# sensor-board_v1_21.net
KiCad netlist of a schematic drawn in EAGLE
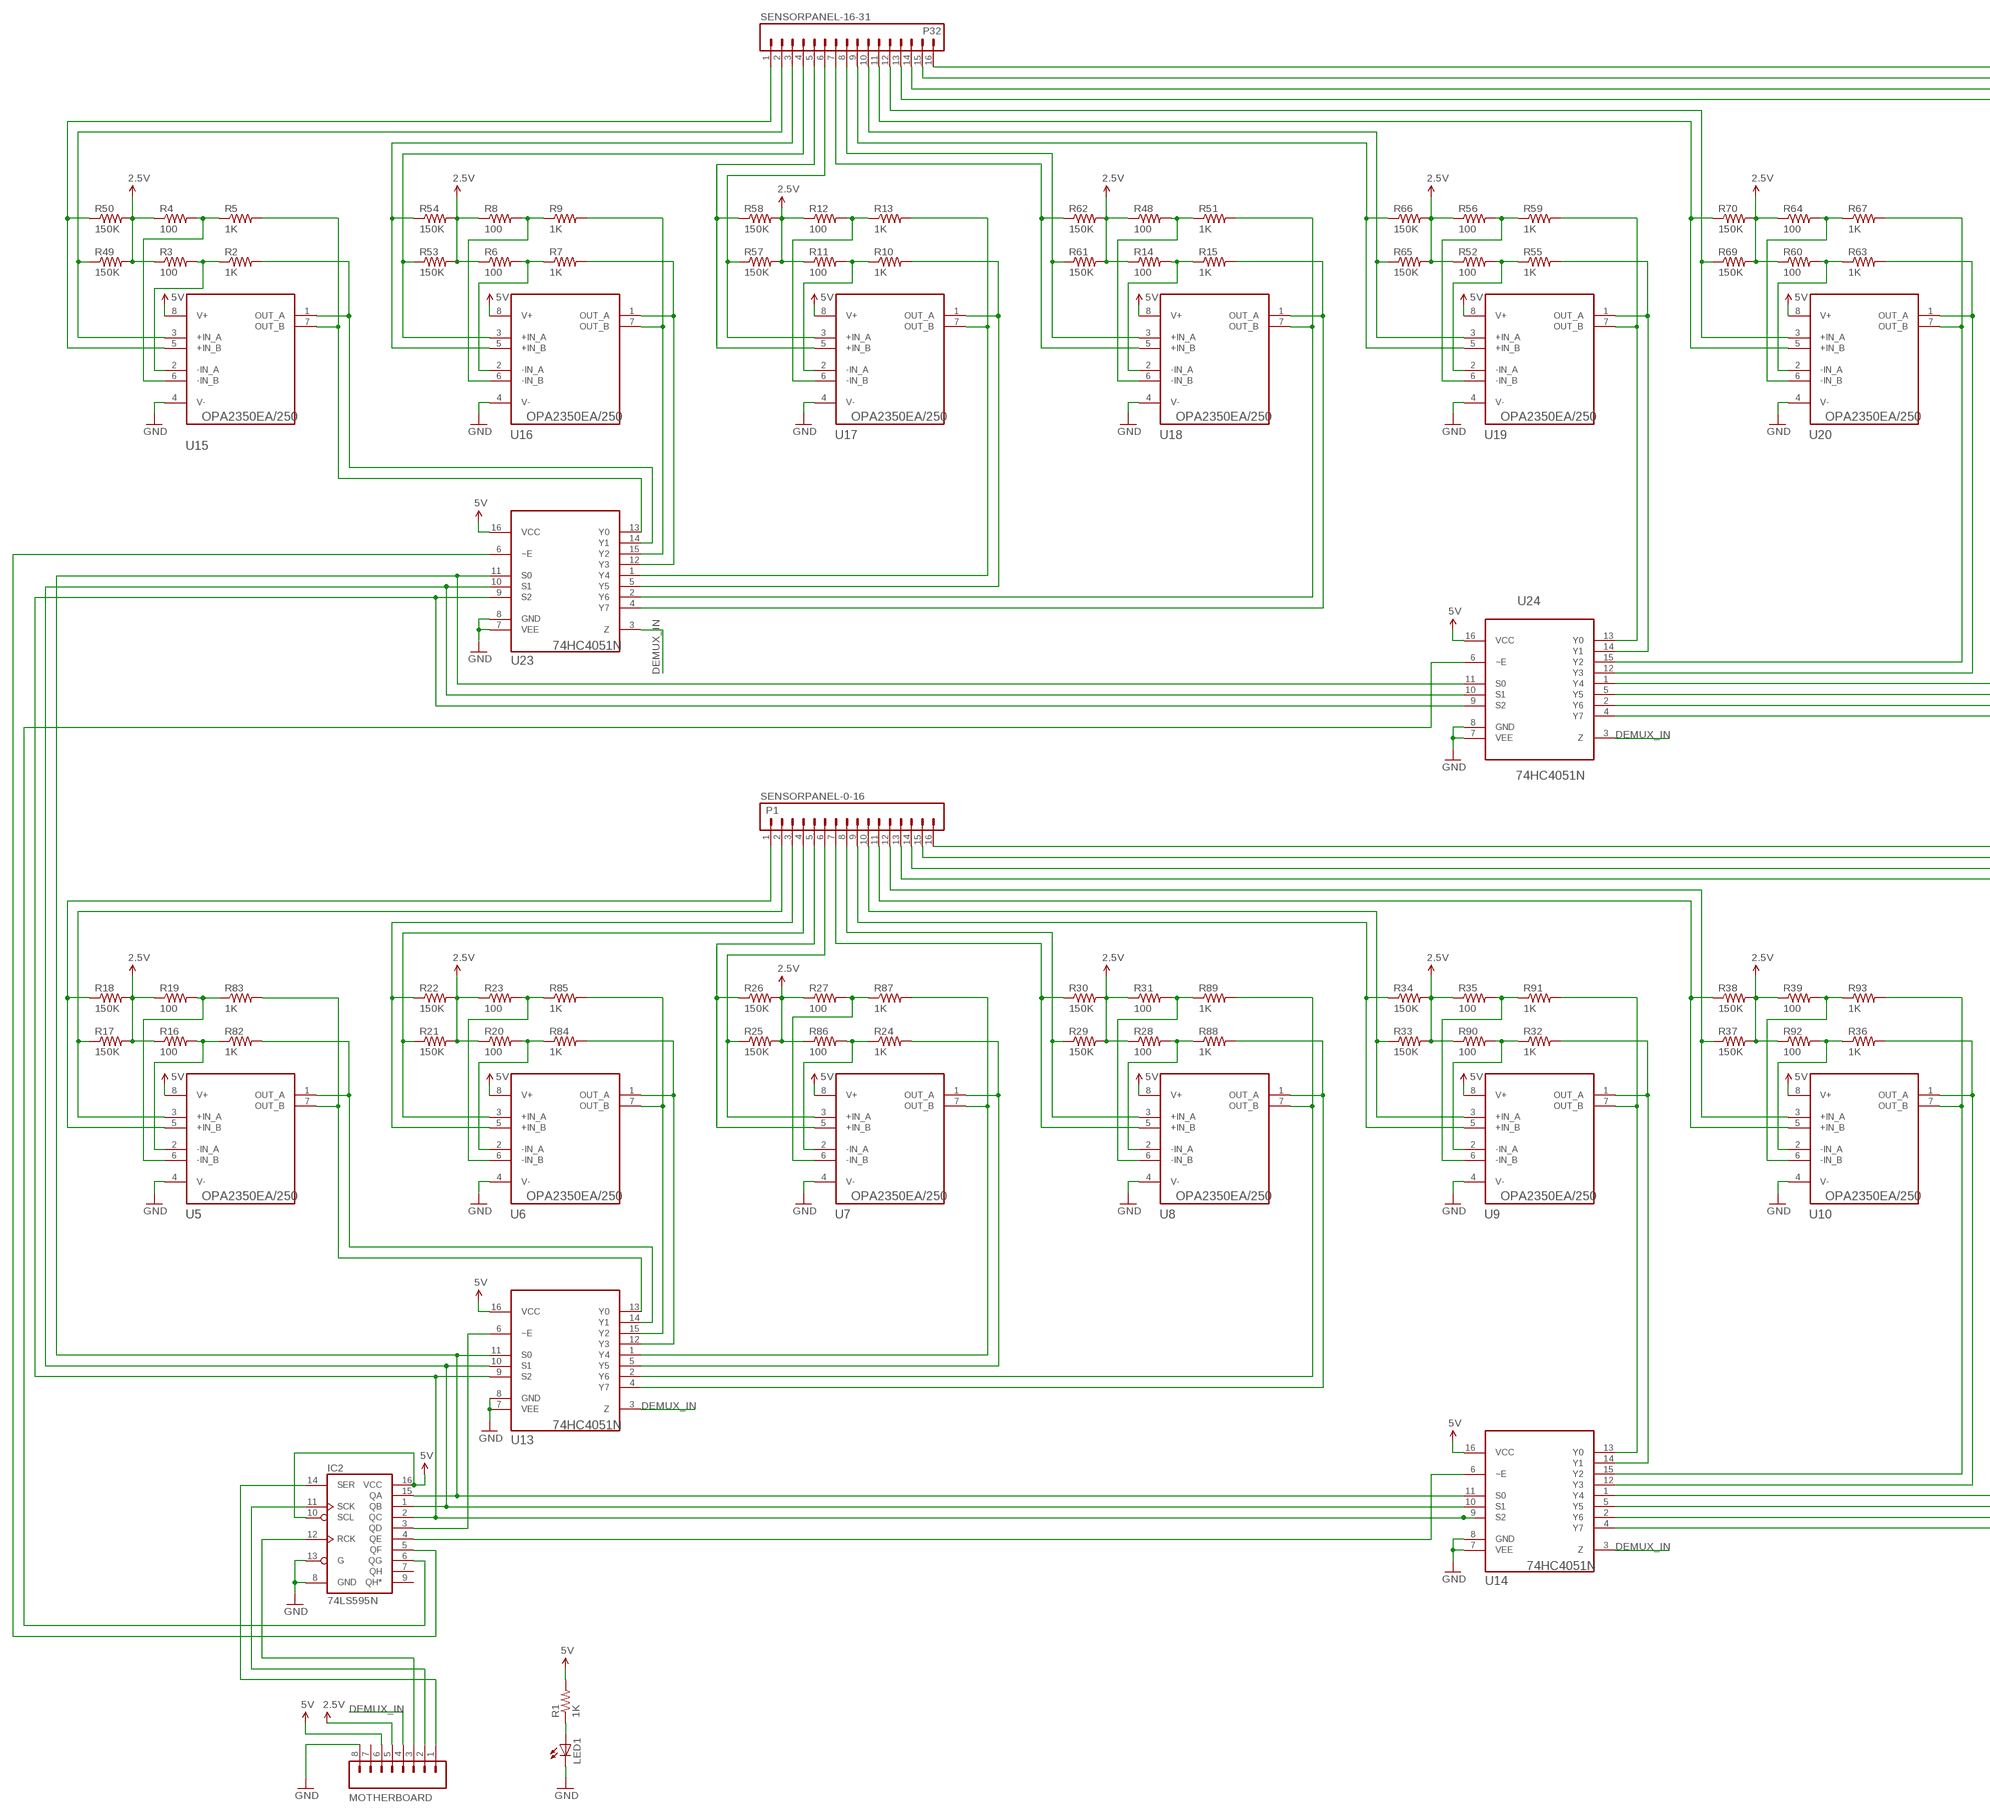
[diagram p0: schematic, sheet 1, part 1 of 2]
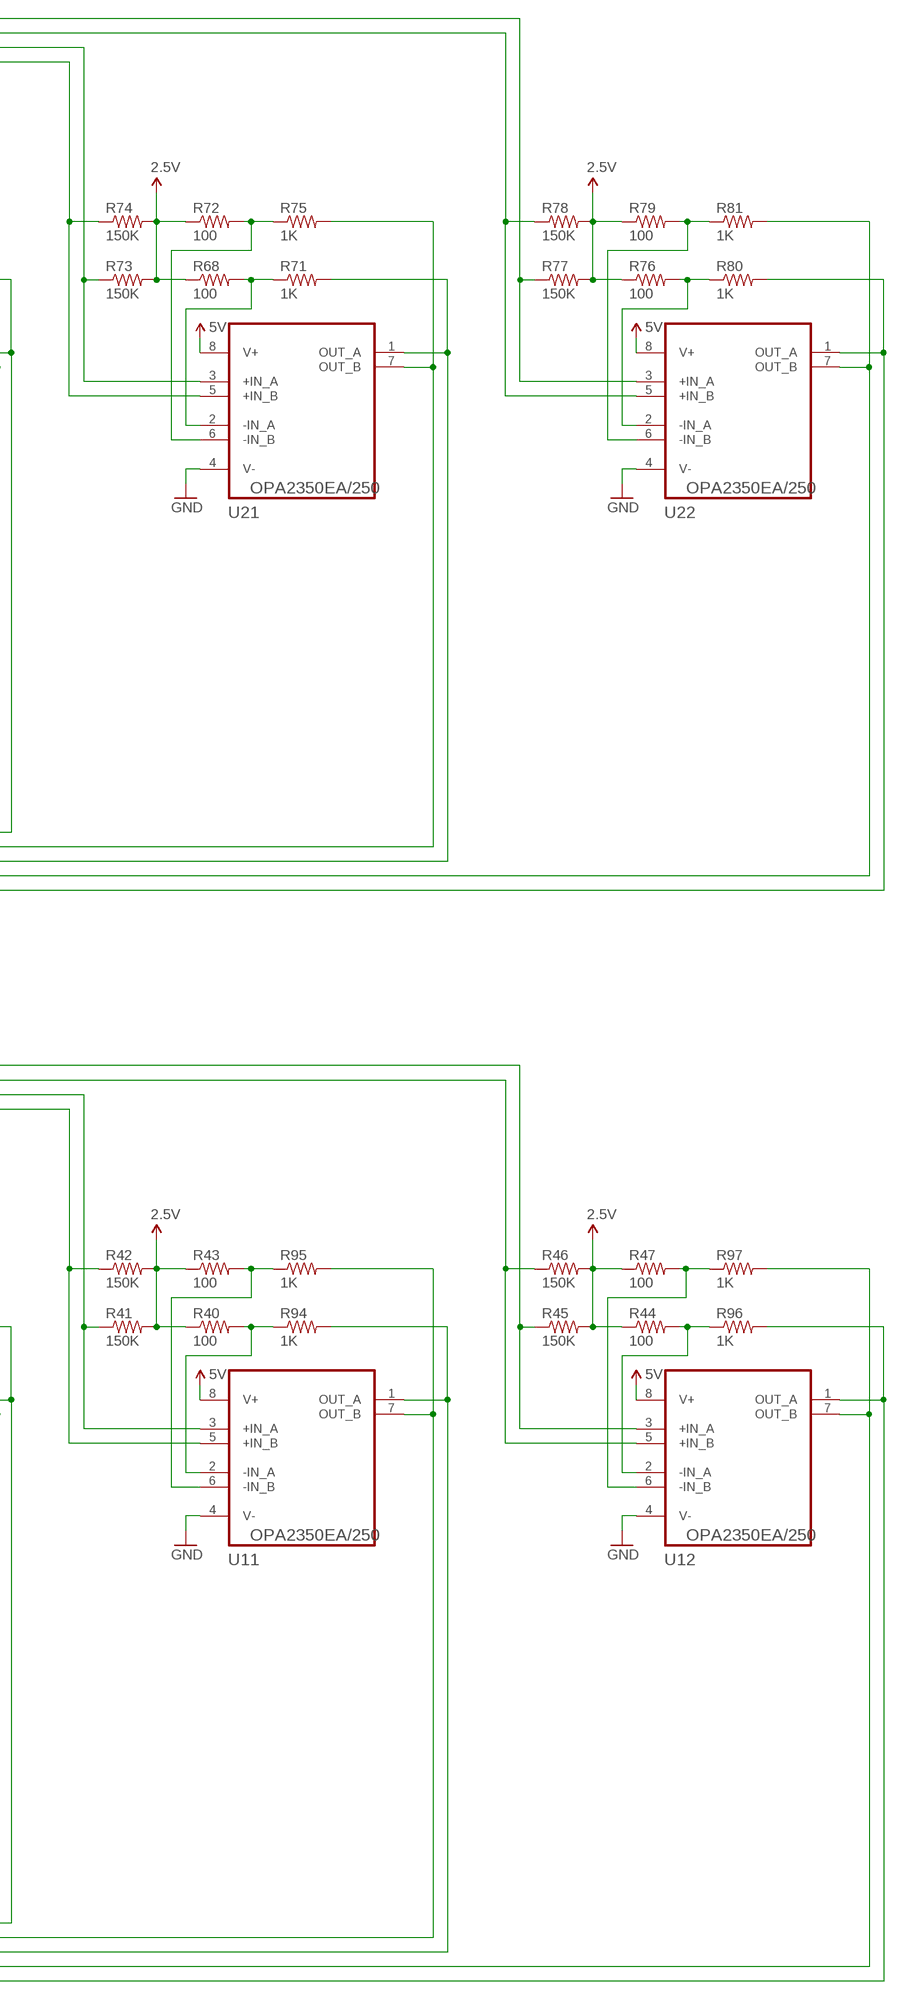
[diagram p1: schematic, sheet 1, part 2 of 2]

(export (version "E")
  (design (tool "Eeschema 10.0.6"))
  (components
    (comp (ref "IC2")
      (value "74LS595N")
      (footprint "eagle-import:DIL16")
      (libsource (lib "eagle-import") (part "74595NLS"))
    )
    (comp (ref "LED1")
      (value "LED0603")
      (footprint "eagle-import:LED-0603")
      (libsource (lib "eagle-import") (part "LED0603"))
    )
    (comp (ref "MOTHERBOARD")
      (value "M08LONGPADS")
      (footprint "eagle-import:1X08_LONGPADS")
      (libsource (lib "eagle-import") (part "M08LONGPADS"))
    )
    (comp (ref "R1")
      (value "1K")
      (footprint "eagle-import:0805")
      (libsource (lib "eagle-import") (part "RESISTOR0805-RES"))
    )
    (comp (ref "R2")
      (value "1K")
      (footprint "eagle-import:0805")
      (libsource (lib "eagle-import") (part "RESISTOR0805-RES"))
    )
    (comp (ref "R3")
      (value "100")
      (footprint "eagle-import:0805")
      (libsource (lib "eagle-import") (part "RESISTOR0805-RES"))
    )
    (comp (ref "R4")
      (value "100")
      (footprint "eagle-import:0805")
      (libsource (lib "eagle-import") (part "RESISTOR0805-RES"))
    )
    (comp (ref "R5")
      (value "1K")
      (footprint "eagle-import:0805")
      (libsource (lib "eagle-import") (part "RESISTOR0805-RES"))
    )
    (comp (ref "R6")
      (value "100")
      (footprint "eagle-import:0805")
      (libsource (lib "eagle-import") (part "RESISTOR0805-RES"))
    )
    (comp (ref "R7")
      (value "1K")
      (footprint "eagle-import:0805")
      (libsource (lib "eagle-import") (part "RESISTOR0805-RES"))
    )
    (comp (ref "R8")
      (value "100")
      (footprint "eagle-import:0805")
      (libsource (lib "eagle-import") (part "RESISTOR0805-RES"))
    )
    (comp (ref "R9")
      (value "1K")
      (footprint "eagle-import:0805")
      (libsource (lib "eagle-import") (part "RESISTOR0805-RES"))
    )
    (comp (ref "R10")
      (value "1K")
      (footprint "eagle-import:0805")
      (libsource (lib "eagle-import") (part "RESISTOR0805-RES"))
    )
    (comp (ref "R11")
      (value "100")
      (footprint "eagle-import:0805")
      (libsource (lib "eagle-import") (part "RESISTOR0805-RES"))
    )
    (comp (ref "R12")
      (value "100")
      (footprint "eagle-import:0805")
      (libsource (lib "eagle-import") (part "RESISTOR0805-RES"))
    )
    (comp (ref "R13")
      (value "1K")
      (footprint "eagle-import:0805")
      (libsource (lib "eagle-import") (part "RESISTOR0805-RES"))
    )
    (comp (ref "R14")
      (value "100")
      (footprint "eagle-import:0805")
      (libsource (lib "eagle-import") (part "RESISTOR0805-RES"))
    )
    (comp (ref "R15")
      (value "1K")
      (footprint "eagle-import:0805")
      (libsource (lib "eagle-import") (part "RESISTOR0805-RES"))
    )
    (comp (ref "R16")
      (value "100")
      (footprint "eagle-import:0805")
      (libsource (lib "eagle-import") (part "RESISTOR0805-RES"))
    )
    (comp (ref "R17")
      (value "150K")
      (footprint "eagle-import:0805")
      (libsource (lib "eagle-import") (part "RESISTOR0805-RES"))
    )
    (comp (ref "R18")
      (value "150K")
      (footprint "eagle-import:0805")
      (libsource (lib "eagle-import") (part "RESISTOR0805-RES"))
    )
    (comp (ref "R19")
      (value "100")
      (footprint "eagle-import:0805")
      (libsource (lib "eagle-import") (part "RESISTOR0805-RES"))
    )
    (comp (ref "R20")
      (value "100")
      (footprint "eagle-import:0805")
      (libsource (lib "eagle-import") (part "RESISTOR0805-RES"))
    )
    (comp (ref "R21")
      (value "150K")
      (footprint "eagle-import:0805")
      (libsource (lib "eagle-import") (part "RESISTOR0805-RES"))
    )
    (comp (ref "R22")
      (value "150K")
      (footprint "eagle-import:0805")
      (libsource (lib "eagle-import") (part "RESISTOR0805-RES"))
    )
    (comp (ref "R23")
      (value "100")
      (footprint "eagle-import:0805")
      (libsource (lib "eagle-import") (part "RESISTOR0805-RES"))
    )
    (comp (ref "R24")
      (value "1K")
      (footprint "eagle-import:0805")
      (libsource (lib "eagle-import") (part "RESISTOR0805-RES"))
    )
    (comp (ref "R25")
      (value "150K")
      (footprint "eagle-import:0805")
      (libsource (lib "eagle-import") (part "RESISTOR0805-RES"))
    )
    (comp (ref "R26")
      (value "150K")
      (footprint "eagle-import:0805")
      (libsource (lib "eagle-import") (part "RESISTOR0805-RES"))
    )
    (comp (ref "R27")
      (value "100")
      (footprint "eagle-import:0805")
      (libsource (lib "eagle-import") (part "RESISTOR0805-RES"))
    )
    (comp (ref "R28")
      (value "100")
      (footprint "eagle-import:0805")
      (libsource (lib "eagle-import") (part "RESISTOR0805-RES"))
    )
    (comp (ref "R29")
      (value "150K")
      (footprint "eagle-import:0805")
      (libsource (lib "eagle-import") (part "RESISTOR0805-RES"))
    )
    (comp (ref "R30")
      (value "150K")
      (footprint "eagle-import:0805")
      (libsource (lib "eagle-import") (part "RESISTOR0805-RES"))
    )
    (comp (ref "R31")
      (value "100")
      (footprint "eagle-import:0805")
      (libsource (lib "eagle-import") (part "RESISTOR0805-RES"))
    )
    (comp (ref "R32")
      (value "1K")
      (footprint "eagle-import:0805")
      (libsource (lib "eagle-import") (part "RESISTOR0805-RES"))
    )
    (comp (ref "R33")
      (value "150K")
      (footprint "eagle-import:0805")
      (libsource (lib "eagle-import") (part "RESISTOR0805-RES"))
    )
    (comp (ref "R34")
      (value "150K")
      (footprint "eagle-import:0805")
      (libsource (lib "eagle-import") (part "RESISTOR0805-RES"))
    )
    (comp (ref "R35")
      (value "100")
      (footprint "eagle-import:0805")
      (libsource (lib "eagle-import") (part "RESISTOR0805-RES"))
    )
    (comp (ref "R36")
      (value "1K")
      (footprint "eagle-import:0805")
      (libsource (lib "eagle-import") (part "RESISTOR0805-RES"))
    )
    (comp (ref "R37")
      (value "150K")
      (footprint "eagle-import:0805")
      (libsource (lib "eagle-import") (part "RESISTOR0805-RES"))
    )
    (comp (ref "R38")
      (value "150K")
      (footprint "eagle-import:0805")
      (libsource (lib "eagle-import") (part "RESISTOR0805-RES"))
    )
    (comp (ref "R39")
      (value "100")
      (footprint "eagle-import:0805")
      (libsource (lib "eagle-import") (part "RESISTOR0805-RES"))
    )
    (comp (ref "R40")
      (value "100")
      (footprint "eagle-import:0805")
      (libsource (lib "eagle-import") (part "RESISTOR0805-RES"))
    )
    (comp (ref "R41")
      (value "150K")
      (footprint "eagle-import:0805")
      (libsource (lib "eagle-import") (part "RESISTOR0805-RES"))
    )
    (comp (ref "R42")
      (value "150K")
      (footprint "eagle-import:0805")
      (libsource (lib "eagle-import") (part "RESISTOR0805-RES"))
    )
    (comp (ref "R43")
      (value "100")
      (footprint "eagle-import:0805")
      (libsource (lib "eagle-import") (part "RESISTOR0805-RES"))
    )
    (comp (ref "R44")
      (value "100")
      (footprint "eagle-import:0805")
      (libsource (lib "eagle-import") (part "RESISTOR0805-RES"))
    )
    (comp (ref "R45")
      (value "150K")
      (footprint "eagle-import:0805")
      (libsource (lib "eagle-import") (part "RESISTOR0805-RES"))
    )
    (comp (ref "R46")
      (value "150K")
      (footprint "eagle-import:0805")
      (libsource (lib "eagle-import") (part "RESISTOR0805-RES"))
    )
    (comp (ref "R47")
      (value "100")
      (footprint "eagle-import:0805")
      (libsource (lib "eagle-import") (part "RESISTOR0805-RES"))
    )
    (comp (ref "R48")
      (value "100")
      (footprint "eagle-import:0805")
      (libsource (lib "eagle-import") (part "RESISTOR0805-RES"))
    )
    (comp (ref "R49")
      (value "150K")
      (footprint "eagle-import:0805")
      (libsource (lib "eagle-import") (part "RESISTOR0805-RES"))
    )
    (comp (ref "R50")
      (value "150K")
      (footprint "eagle-import:0805")
      (libsource (lib "eagle-import") (part "RESISTOR0805-RES"))
    )
    (comp (ref "R51")
      (value "1K")
      (footprint "eagle-import:0805")
      (libsource (lib "eagle-import") (part "RESISTOR0805-RES"))
    )
    (comp (ref "R52")
      (value "100")
      (footprint "eagle-import:0805")
      (libsource (lib "eagle-import") (part "RESISTOR0805-RES"))
    )
    (comp (ref "R53")
      (value "150K")
      (footprint "eagle-import:0805")
      (libsource (lib "eagle-import") (part "RESISTOR0805-RES"))
    )
    (comp (ref "R54")
      (value "150K")
      (footprint "eagle-import:0805")
      (libsource (lib "eagle-import") (part "RESISTOR0805-RES"))
    )
    (comp (ref "R55")
      (value "1K")
      (footprint "eagle-import:0805")
      (libsource (lib "eagle-import") (part "RESISTOR0805-RES"))
    )
    (comp (ref "R56")
      (value "100")
      (footprint "eagle-import:0805")
      (libsource (lib "eagle-import") (part "RESISTOR0805-RES"))
    )
    (comp (ref "R57")
      (value "150K")
      (footprint "eagle-import:0805")
      (libsource (lib "eagle-import") (part "RESISTOR0805-RES"))
    )
    (comp (ref "R58")
      (value "150K")
      (footprint "eagle-import:0805")
      (libsource (lib "eagle-import") (part "RESISTOR0805-RES"))
    )
    (comp (ref "R59")
      (value "1K")
      (footprint "eagle-import:0805")
      (libsource (lib "eagle-import") (part "RESISTOR0805-RES"))
    )
    (comp (ref "R60")
      (value "100")
      (footprint "eagle-import:0805")
      (libsource (lib "eagle-import") (part "RESISTOR0805-RES"))
    )
    (comp (ref "R61")
      (value "150K")
      (footprint "eagle-import:0805")
      (libsource (lib "eagle-import") (part "RESISTOR0805-RES"))
    )
    (comp (ref "R62")
      (value "150K")
      (footprint "eagle-import:0805")
      (libsource (lib "eagle-import") (part "RESISTOR0805-RES"))
    )
    (comp (ref "R63")
      (value "1K")
      (footprint "eagle-import:0805")
      (libsource (lib "eagle-import") (part "RESISTOR0805-RES"))
    )
    (comp (ref "R64")
      (value "100")
      (footprint "eagle-import:0805")
      (libsource (lib "eagle-import") (part "RESISTOR0805-RES"))
    )
    (comp (ref "R65")
      (value "150K")
      (footprint "eagle-import:0805")
      (libsource (lib "eagle-import") (part "RESISTOR0805-RES"))
    )
    (comp (ref "R66")
      (value "150K")
      (footprint "eagle-import:0805")
      (libsource (lib "eagle-import") (part "RESISTOR0805-RES"))
    )
    (comp (ref "R67")
      (value "1K")
      (footprint "eagle-import:0805")
      (libsource (lib "eagle-import") (part "RESISTOR0805-RES"))
    )
    (comp (ref "R68")
      (value "100")
      (footprint "eagle-import:0805")
      (libsource (lib "eagle-import") (part "RESISTOR0805-RES"))
    )
    (comp (ref "R69")
      (value "150K")
      (footprint "eagle-import:0805")
      (libsource (lib "eagle-import") (part "RESISTOR0805-RES"))
    )
    (comp (ref "R70")
      (value "150K")
      (footprint "eagle-import:0805")
      (libsource (lib "eagle-import") (part "RESISTOR0805-RES"))
    )
    (comp (ref "R71")
      (value "1K")
      (footprint "eagle-import:0805")
      (libsource (lib "eagle-import") (part "RESISTOR0805-RES"))
    )
    (comp (ref "R72")
      (value "100")
      (footprint "eagle-import:0805")
      (libsource (lib "eagle-import") (part "RESISTOR0805-RES"))
    )
    (comp (ref "R73")
      (value "150K")
      (footprint "eagle-import:0805")
      (libsource (lib "eagle-import") (part "RESISTOR0805-RES"))
    )
    (comp (ref "R74")
      (value "150K")
      (footprint "eagle-import:0805")
      (libsource (lib "eagle-import") (part "RESISTOR0805-RES"))
    )
    (comp (ref "R75")
      (value "1K")
      (footprint "eagle-import:0805")
      (libsource (lib "eagle-import") (part "RESISTOR0805-RES"))
    )
    (comp (ref "R76")
      (value "100")
      (footprint "eagle-import:0805")
      (libsource (lib "eagle-import") (part "RESISTOR0805-RES"))
    )
    (comp (ref "R77")
      (value "150K")
      (footprint "eagle-import:0805")
      (libsource (lib "eagle-import") (part "RESISTOR0805-RES"))
    )
    (comp (ref "R78")
      (value "150K")
      (footprint "eagle-import:0805")
      (libsource (lib "eagle-import") (part "RESISTOR0805-RES"))
    )
    (comp (ref "R79")
      (value "100")
      (footprint "eagle-import:0805")
      (libsource (lib "eagle-import") (part "RESISTOR0805-RES"))
    )
    (comp (ref "R80")
      (value "1K")
      (footprint "eagle-import:0805")
      (libsource (lib "eagle-import") (part "RESISTOR0805-RES"))
    )
    (comp (ref "R81")
      (value "1K")
      (footprint "eagle-import:0805")
      (libsource (lib "eagle-import") (part "RESISTOR0805-RES"))
    )
    (comp (ref "R82")
      (value "1K")
      (footprint "eagle-import:0805")
      (libsource (lib "eagle-import") (part "RESISTOR0805-RES"))
    )
    (comp (ref "R83")
      (value "1K")
      (footprint "eagle-import:0805")
      (libsource (lib "eagle-import") (part "RESISTOR0805-RES"))
    )
    (comp (ref "R84")
      (value "1K")
      (footprint "eagle-import:0805")
      (libsource (lib "eagle-import") (part "RESISTOR0805-RES"))
    )
    (comp (ref "R85")
      (value "1K")
      (footprint "eagle-import:0805")
      (libsource (lib "eagle-import") (part "RESISTOR0805-RES"))
    )
    (comp (ref "R86")
      (value "100")
      (footprint "eagle-import:0805")
      (libsource (lib "eagle-import") (part "RESISTOR0805-RES"))
    )
    (comp (ref "R87")
      (value "1K")
      (footprint "eagle-import:0805")
      (libsource (lib "eagle-import") (part "RESISTOR0805-RES"))
    )
    (comp (ref "R88")
      (value "1K")
      (footprint "eagle-import:0805")
      (libsource (lib "eagle-import") (part "RESISTOR0805-RES"))
    )
    (comp (ref "R89")
      (value "1K")
      (footprint "eagle-import:0805")
      (libsource (lib "eagle-import") (part "RESISTOR0805-RES"))
    )
    (comp (ref "R90")
      (value "100")
      (footprint "eagle-import:0805")
      (libsource (lib "eagle-import") (part "RESISTOR0805-RES"))
    )
    (comp (ref "R91")
      (value "1K")
      (footprint "eagle-import:0805")
      (libsource (lib "eagle-import") (part "RESISTOR0805-RES"))
    )
    (comp (ref "R92")
      (value "100")
      (footprint "eagle-import:0805")
      (libsource (lib "eagle-import") (part "RESISTOR0805-RES"))
    )
    (comp (ref "R93")
      (value "1K")
      (footprint "eagle-import:0805")
      (libsource (lib "eagle-import") (part "RESISTOR0805-RES"))
    )
    (comp (ref "R94")
      (value "1K")
      (footprint "eagle-import:0805")
      (libsource (lib "eagle-import") (part "RESISTOR0805-RES"))
    )
    (comp (ref "R95")
      (value "1K")
      (footprint "eagle-import:0805")
      (libsource (lib "eagle-import") (part "RESISTOR0805-RES"))
    )
    (comp (ref "R96")
      (value "1K")
      (footprint "eagle-import:0805")
      (libsource (lib "eagle-import") (part "RESISTOR0805-RES"))
    )
    (comp (ref "R97")
      (value "1K")
      (footprint "eagle-import:0805")
      (libsource (lib "eagle-import") (part "RESISTOR0805-RES"))
    )
    (comp (ref "SENSORPANEL-0-16")
      (value "P1")
      (footprint "eagle-import:1X16_LOCK")
      (libsource (lib "eagle-import") (part "M16LOCK"))
    )
    (comp (ref "SENSORPANEL-16-31")
      (value "P32")
      (footprint "eagle-import:1X16_LOCK")
      (libsource (lib "eagle-import") (part "M16LOCK"))
    )
    (comp (ref "U5")
      (value "OPA2350EA/250")
      (footprint "eagle-import:SOP65P490X110-8N")
      (libsource (lib "eagle-import") (part "OPA2350EA/250"))
    )
    (comp (ref "U6")
      (value "OPA2350EA/250")
      (footprint "eagle-import:SOP65P490X110-8N")
      (libsource (lib "eagle-import") (part "OPA2350EA/250"))
    )
    (comp (ref "U7")
      (value "OPA2350EA/250")
      (footprint "eagle-import:SOP65P490X110-8N")
      (libsource (lib "eagle-import") (part "OPA2350EA/250"))
    )
    (comp (ref "U8")
      (value "OPA2350EA/250")
      (footprint "eagle-import:SOP65P490X110-8N")
      (libsource (lib "eagle-import") (part "OPA2350EA/250"))
    )
    (comp (ref "U9")
      (value "OPA2350EA/250")
      (footprint "eagle-import:SOP65P490X110-8N")
      (libsource (lib "eagle-import") (part "OPA2350EA/250"))
    )
    (comp (ref "U10")
      (value "OPA2350EA/250")
      (footprint "eagle-import:SOP65P490X110-8N")
      (libsource (lib "eagle-import") (part "OPA2350EA/250"))
    )
    (comp (ref "U11")
      (value "OPA2350EA/250")
      (footprint "eagle-import:SOP65P490X110-8N")
      (libsource (lib "eagle-import") (part "OPA2350EA/250"))
    )
    (comp (ref "U12")
      (value "OPA2350EA/250")
      (footprint "eagle-import:SOP65P490X110-8N")
      (libsource (lib "eagle-import") (part "OPA2350EA/250"))
    )
    (comp (ref "U13")
      (value "74HC4051N")
      (footprint "eagle-import:DIP254P762X420-16")
      (libsource (lib "eagle-import") (part "74HC4051N"))
    )
    (comp (ref "U14")
      (value "74HC4051N")
      (footprint "eagle-import:DIP254P762X420-16")
      (libsource (lib "eagle-import") (part "74HC4051N"))
    )
    (comp (ref "U15")
      (value "OPA2350EA/250")
      (footprint "eagle-import:SOP65P490X110-8N")
      (libsource (lib "eagle-import") (part "OPA2350EA/250"))
    )
    (comp (ref "U16")
      (value "OPA2350EA/250")
      (footprint "eagle-import:SOP65P490X110-8N")
      (libsource (lib "eagle-import") (part "OPA2350EA/250"))
    )
    (comp (ref "U17")
      (value "OPA2350EA/250")
      (footprint "eagle-import:SOP65P490X110-8N")
      (libsource (lib "eagle-import") (part "OPA2350EA/250"))
    )
    (comp (ref "U18")
      (value "OPA2350EA/250")
      (footprint "eagle-import:SOP65P490X110-8N")
      (libsource (lib "eagle-import") (part "OPA2350EA/250"))
    )
    (comp (ref "U19")
      (value "OPA2350EA/250")
      (footprint "eagle-import:SOP65P490X110-8N")
      (libsource (lib "eagle-import") (part "OPA2350EA/250"))
    )
    (comp (ref "U20")
      (value "OPA2350EA/250")
      (footprint "eagle-import:SOP65P490X110-8N")
      (libsource (lib "eagle-import") (part "OPA2350EA/250"))
    )
    (comp (ref "U21")
      (value "OPA2350EA/250")
      (footprint "eagle-import:SOP65P490X110-8N")
      (libsource (lib "eagle-import") (part "OPA2350EA/250"))
    )
    (comp (ref "U22")
      (value "OPA2350EA/250")
      (footprint "eagle-import:SOP65P490X110-8N")
      (libsource (lib "eagle-import") (part "OPA2350EA/250"))
    )
    (comp (ref "U23")
      (value "74HC4051N")
      (footprint "eagle-import:DIP254P762X420-16")
      (libsource (lib "eagle-import") (part "74HC4051N"))
    )
    (comp (ref "U24")
      (value "74HC4051N")
      (footprint "eagle-import:DIP254P762X420-16")
      (libsource (lib "eagle-import") (part "74HC4051N"))
    )
  )
  (nets
    (net (code "1") (name "/DEMUX_IN") (class "Default")
      (node (ref "MOTHERBOARD") (pin "4") (pinfunction "4_4") (pintype "passive"))
      (node (ref "U13") (pin "3") (pinfunction "Z_3") (pintype "bidirectional"))
      (node (ref "U14") (pin "3") (pinfunction "Z_3") (pintype "bidirectional"))
      (node (ref "U23") (pin "3") (pinfunction "Z_3") (pintype "bidirectional"))
      (node (ref "U24") (pin "3") (pinfunction "Z_3") (pintype "bidirectional"))
    )
    (net (code "2") (name "2.5V") (class "Default")
      (node (ref "MOTHERBOARD") (pin "5") (pinfunction "5_5") (pintype "passive"))
      (node (ref "R11") (pin "1") (pinfunction "1_1") (pintype "passive"))
      (node (ref "R12") (pin "1") (pinfunction "1_1") (pintype "passive"))
      (node (ref "R14") (pin "1") (pinfunction "1_1") (pintype "passive"))
      (node (ref "R16") (pin "1") (pinfunction "1_1") (pintype "passive"))
      (node (ref "R17") (pin "2") (pinfunction "2_2") (pintype "passive"))
      (node (ref "R18") (pin "2") (pinfunction "2_2") (pintype "passive"))
      (node (ref "R19") (pin "1") (pinfunction "1_1") (pintype "passive"))
      (node (ref "R20") (pin "1") (pinfunction "1_1") (pintype "passive"))
      (node (ref "R21") (pin "2") (pinfunction "2_2") (pintype "passive"))
      (node (ref "R22") (pin "2") (pinfunction "2_2") (pintype "passive"))
      (node (ref "R23") (pin "1") (pinfunction "1_1") (pintype "passive"))
      (node (ref "R25") (pin "2") (pinfunction "2_2") (pintype "passive"))
      (node (ref "R26") (pin "2") (pinfunction "2_2") (pintype "passive"))
      (node (ref "R27") (pin "1") (pinfunction "1_1") (pintype "passive"))
      (node (ref "R28") (pin "1") (pinfunction "1_1") (pintype "passive"))
      (node (ref "R29") (pin "2") (pinfunction "2_2") (pintype "passive"))
      (node (ref "R3") (pin "1") (pinfunction "1_1") (pintype "passive"))
      (node (ref "R30") (pin "2") (pinfunction "2_2") (pintype "passive"))
      (node (ref "R31") (pin "1") (pinfunction "1_1") (pintype "passive"))
      (node (ref "R33") (pin "2") (pinfunction "2_2") (pintype "passive"))
      (node (ref "R34") (pin "2") (pinfunction "2_2") (pintype "passive"))
      (node (ref "R35") (pin "1") (pinfunction "1_1") (pintype "passive"))
      (node (ref "R37") (pin "2") (pinfunction "2_2") (pintype "passive"))
      (node (ref "R38") (pin "2") (pinfunction "2_2") (pintype "passive"))
      (node (ref "R39") (pin "1") (pinfunction "1_1") (pintype "passive"))
      (node (ref "R4") (pin "1") (pinfunction "1_1") (pintype "passive"))
      (node (ref "R40") (pin "1") (pinfunction "1_1") (pintype "passive"))
      (node (ref "R41") (pin "2") (pinfunction "2_2") (pintype "passive"))
      (node (ref "R42") (pin "2") (pinfunction "2_2") (pintype "passive"))
      (node (ref "R43") (pin "1") (pinfunction "1_1") (pintype "passive"))
      (node (ref "R44") (pin "1") (pinfunction "1_1") (pintype "passive"))
      (node (ref "R45") (pin "2") (pinfunction "2_2") (pintype "passive"))
      (node (ref "R46") (pin "2") (pinfunction "2_2") (pintype "passive"))
      (node (ref "R47") (pin "1") (pinfunction "1_1") (pintype "passive"))
      (node (ref "R48") (pin "1") (pinfunction "1_1") (pintype "passive"))
      (node (ref "R49") (pin "2") (pinfunction "2_2") (pintype "passive"))
      (node (ref "R50") (pin "2") (pinfunction "2_2") (pintype "passive"))
      (node (ref "R52") (pin "1") (pinfunction "1_1") (pintype "passive"))
      (node (ref "R53") (pin "2") (pinfunction "2_2") (pintype "passive"))
      (node (ref "R54") (pin "2") (pinfunction "2_2") (pintype "passive"))
      (node (ref "R56") (pin "1") (pinfunction "1_1") (pintype "passive"))
      (node (ref "R57") (pin "2") (pinfunction "2_2") (pintype "passive"))
      (node (ref "R58") (pin "2") (pinfunction "2_2") (pintype "passive"))
      (node (ref "R6") (pin "1") (pinfunction "1_1") (pintype "passive"))
      (node (ref "R60") (pin "1") (pinfunction "1_1") (pintype "passive"))
      (node (ref "R61") (pin "2") (pinfunction "2_2") (pintype "passive"))
      (node (ref "R62") (pin "2") (pinfunction "2_2") (pintype "passive"))
      (node (ref "R64") (pin "1") (pinfunction "1_1") (pintype "passive"))
      (node (ref "R65") (pin "2") (pinfunction "2_2") (pintype "passive"))
      (node (ref "R66") (pin "2") (pinfunction "2_2") (pintype "passive"))
      (node (ref "R68") (pin "1") (pinfunction "1_1") (pintype "passive"))
      (node (ref "R69") (pin "2") (pinfunction "2_2") (pintype "passive"))
      (node (ref "R70") (pin "2") (pinfunction "2_2") (pintype "passive"))
      (node (ref "R72") (pin "1") (pinfunction "1_1") (pintype "passive"))
      (node (ref "R73") (pin "2") (pinfunction "2_2") (pintype "passive"))
      (node (ref "R74") (pin "2") (pinfunction "2_2") (pintype "passive"))
      (node (ref "R76") (pin "1") (pinfunction "1_1") (pintype "passive"))
      (node (ref "R77") (pin "2") (pinfunction "2_2") (pintype "passive"))
      (node (ref "R78") (pin "2") (pinfunction "2_2") (pintype "passive"))
      (node (ref "R79") (pin "1") (pinfunction "1_1") (pintype "passive"))
      (node (ref "R8") (pin "1") (pinfunction "1_1") (pintype "passive"))
      (node (ref "R86") (pin "1") (pinfunction "1_1") (pintype "passive"))
      (node (ref "R90") (pin "1") (pinfunction "1_1") (pintype "passive"))
      (node (ref "R92") (pin "1") (pinfunction "1_1") (pintype "passive"))
    )
    (net (code "3") (name "5V") (class "Default")
      (node (ref "IC2") (pin "10") (pinfunction "SCL_10") (pintype "input"))
      (node (ref "IC2") (pin "16") (pinfunction "VCC_16") (pintype "power_in"))
      (node (ref "MOTHERBOARD") (pin "6") (pinfunction "6_6") (pintype "passive"))
      (node (ref "R1") (pin "2") (pinfunction "2_2") (pintype "passive"))
      (node (ref "U10") (pin "8") (pinfunction "V+_8") (pintype "power_in"))
      (node (ref "U11") (pin "8") (pinfunction "V+_8") (pintype "power_in"))
      (node (ref "U12") (pin "8") (pinfunction "V+_8") (pintype "power_in"))
      (node (ref "U13") (pin "16") (pinfunction "VCC_16") (pintype "power_in"))
      (node (ref "U14") (pin "16") (pinfunction "VCC_16") (pintype "power_in"))
      (node (ref "U15") (pin "8") (pinfunction "V+_8") (pintype "power_in"))
      (node (ref "U16") (pin "8") (pinfunction "V+_8") (pintype "power_in"))
      (node (ref "U17") (pin "8") (pinfunction "V+_8") (pintype "power_in"))
      (node (ref "U18") (pin "8") (pinfunction "V+_8") (pintype "power_in"))
      (node (ref "U19") (pin "8") (pinfunction "V+_8") (pintype "power_in"))
      (node (ref "U20") (pin "8") (pinfunction "V+_8") (pintype "power_in"))
      (node (ref "U21") (pin "8") (pinfunction "V+_8") (pintype "power_in"))
      (node (ref "U22") (pin "8") (pinfunction "V+_8") (pintype "power_in"))
      (node (ref "U23") (pin "16") (pinfunction "VCC_16") (pintype "power_in"))
      (node (ref "U24") (pin "16") (pinfunction "VCC_16") (pintype "power_in"))
      (node (ref "U5") (pin "8") (pinfunction "V+_8") (pintype "power_in"))
      (node (ref "U6") (pin "8") (pinfunction "V+_8") (pintype "power_in"))
      (node (ref "U7") (pin "8") (pinfunction "V+_8") (pintype "power_in"))
      (node (ref "U8") (pin "8") (pinfunction "V+_8") (pintype "power_in"))
      (node (ref "U9") (pin "8") (pinfunction "V+_8") (pintype "power_in"))
    )
    (net (code "4") (name "GND") (class "Default")
      (node (ref "IC2") (pin "13") (pinfunction "G_13") (pintype "input"))
      (node (ref "IC2") (pin "8") (pinfunction "GND_8") (pintype "power_in"))
      (node (ref "LED1") (pin "C") (pinfunction "C_C") (pintype "passive"))
      (node (ref "MOTHERBOARD") (pin "8") (pinfunction "8_8") (pintype "passive"))
      (node (ref "U10") (pin "4") (pinfunction "V-_4") (pintype "power_in"))
      (node (ref "U11") (pin "4") (pinfunction "V-_4") (pintype "power_in"))
      (node (ref "U12") (pin "4") (pinfunction "V-_4") (pintype "power_in"))
      (node (ref "U13") (pin "7") (pinfunction "VEE_7") (pintype "power_in"))
      (node (ref "U13") (pin "8") (pinfunction "GND_8") (pintype "passive"))
      (node (ref "U14") (pin "7") (pinfunction "VEE_7") (pintype "power_in"))
      (node (ref "U14") (pin "8") (pinfunction "GND_8") (pintype "passive"))
      (node (ref "U15") (pin "4") (pinfunction "V-_4") (pintype "power_in"))
      (node (ref "U16") (pin "4") (pinfunction "V-_4") (pintype "power_in"))
      (node (ref "U17") (pin "4") (pinfunction "V-_4") (pintype "power_in"))
      (node (ref "U18") (pin "4") (pinfunction "V-_4") (pintype "power_in"))
      (node (ref "U19") (pin "4") (pinfunction "V-_4") (pintype "power_in"))
      (node (ref "U20") (pin "4") (pinfunction "V-_4") (pintype "power_in"))
      (node (ref "U21") (pin "4") (pinfunction "V-_4") (pintype "power_in"))
      (node (ref "U22") (pin "4") (pinfunction "V-_4") (pintype "power_in"))
      (node (ref "U23") (pin "7") (pinfunction "VEE_7") (pintype "power_in"))
      (node (ref "U23") (pin "8") (pinfunction "GND_8") (pintype "passive"))
      (node (ref "U24") (pin "7") (pinfunction "VEE_7") (pintype "power_in"))
      (node (ref "U24") (pin "8") (pinfunction "GND_8") (pintype "passive"))
      (node (ref "U5") (pin "4") (pinfunction "V-_4") (pintype "power_in"))
      (node (ref "U6") (pin "4") (pinfunction "V-_4") (pintype "power_in"))
      (node (ref "U7") (pin "4") (pinfunction "V-_4") (pintype "power_in"))
      (node (ref "U8") (pin "4") (pinfunction "V-_4") (pintype "power_in"))
      (node (ref "U9") (pin "4") (pinfunction "V-_4") (pintype "power_in"))
    )
    (net (code "5") (name "Net-(IC2-QA)") (class "Default")
      (node (ref "IC2") (pin "15") (pinfunction "QA_15") (pintype "tri_state"))
      (node (ref "U13") (pin "11") (pinfunction "S0_11") (pintype "input"))
      (node (ref "U14") (pin "11") (pinfunction "S0_11") (pintype "input"))
      (node (ref "U23") (pin "11") (pinfunction "S0_11") (pintype "input"))
      (node (ref "U24") (pin "11") (pinfunction "S0_11") (pintype "input"))
    )
    (net (code "6") (name "Net-(IC2-QB)") (class "Default")
      (node (ref "IC2") (pin "1") (pinfunction "QB_1") (pintype "tri_state"))
      (node (ref "U13") (pin "10") (pinfunction "S1_10") (pintype "input"))
      (node (ref "U14") (pin "10") (pinfunction "S1_10") (pintype "input"))
      (node (ref "U23") (pin "10") (pinfunction "S1_10") (pintype "input"))
      (node (ref "U24") (pin "10") (pinfunction "S1_10") (pintype "input"))
    )
    (net (code "7") (name "Net-(IC2-QC)") (class "Default")
      (node (ref "IC2") (pin "2") (pinfunction "QC_2") (pintype "tri_state"))
      (node (ref "U13") (pin "9") (pinfunction "S2_9") (pintype "input"))
      (node (ref "U14") (pin "9") (pinfunction "S2_9") (pintype "input"))
      (node (ref "U23") (pin "9") (pinfunction "S2_9") (pintype "input"))
      (node (ref "U24") (pin "9") (pinfunction "S2_9") (pintype "input"))
    )
    (net (code "8") (name "Net-(IC2-QD)") (class "Default")
      (node (ref "IC2") (pin "3") (pinfunction "QD_3") (pintype "tri_state"))
      (node (ref "U13") (pin "6") (pinfunction "~{E}_6") (pintype "input"))
    )
    (net (code "9") (name "Net-(IC2-QE)") (class "Default")
      (node (ref "IC2") (pin "4") (pinfunction "QE_4") (pintype "tri_state"))
      (node (ref "U14") (pin "6") (pinfunction "~{E}_6") (pintype "input"))
    )
    (net (code "10") (name "Net-(IC2-QF)") (class "Default")
      (node (ref "IC2") (pin "5") (pinfunction "QF_5") (pintype "tri_state"))
      (node (ref "U23") (pin "6") (pinfunction "~{E}_6") (pintype "input"))
    )
    (net (code "11") (name "Net-(IC2-QG)") (class "Default")
      (node (ref "IC2") (pin "6") (pinfunction "QG_6") (pintype "tri_state"))
      (node (ref "U24") (pin "6") (pinfunction "~{E}_6") (pintype "input"))
    )
    (net (code "12") (name "Net-(IC2-RCK)") (class "Default")
      (node (ref "IC2") (pin "12") (pinfunction "RCK_12") (pintype "input"))
      (node (ref "MOTHERBOARD") (pin "3") (pinfunction "3_3") (pintype "passive"))
    )
    (net (code "13") (name "Net-(IC2-SCK)") (class "Default")
      (node (ref "IC2") (pin "11") (pinfunction "SCK_11") (pintype "input"))
      (node (ref "MOTHERBOARD") (pin "2") (pinfunction "2_2") (pintype "passive"))
    )
    (net (code "14") (name "Net-(IC2-SER)") (class "Default")
      (node (ref "IC2") (pin "14") (pinfunction "SER_14") (pintype "input"))
      (node (ref "MOTHERBOARD") (pin "1") (pinfunction "1_1") (pintype "passive"))
    )
    (net (code "15") (name "Net-(LED1-PadA)") (class "Default")
      (node (ref "LED1") (pin "A") (pinfunction "A_A") (pintype "passive"))
      (node (ref "R1") (pin "1") (pinfunction "1_1") (pintype "passive"))
    )
    (net (code "16") (name "Net-(U5-+IN_A)") (class "Default")
      (node (ref "R17") (pin "1") (pinfunction "1_1") (pintype "passive"))
      (node (ref "SENSORPANEL-0-16") (pin "2") (pinfunction "2_2") (pintype "passive"))
      (node (ref "U5") (pin "3") (pinfunction "+IN_A_3") (pintype "input"))
    )
    (net (code "17") (name "Net-(U5-+IN_B)") (class "Default")
      (node (ref "R18") (pin "1") (pinfunction "1_1") (pintype "passive"))
      (node (ref "SENSORPANEL-0-16") (pin "1") (pinfunction "1_1") (pintype "passive"))
      (node (ref "U5") (pin "5") (pinfunction "+IN_B_5") (pintype "input"))
    )
    (net (code "18") (name "Net-(U5--IN_A)") (class "Default")
      (node (ref "R16") (pin "2") (pinfunction "2_2") (pintype "passive"))
      (node (ref "R82") (pin "1") (pinfunction "1_1") (pintype "passive"))
      (node (ref "U5") (pin "2") (pinfunction "-IN_A_2") (pintype "input"))
    )
    (net (code "19") (name "Net-(U5--IN_B)") (class "Default")
      (node (ref "R19") (pin "2") (pinfunction "2_2") (pintype "passive"))
      (node (ref "R83") (pin "1") (pinfunction "1_1") (pintype "passive"))
      (node (ref "U5") (pin "6") (pinfunction "-IN_B_6") (pintype "input"))
    )
    (net (code "20") (name "Net-(U6-+IN_A)") (class "Default")
      (node (ref "R21") (pin "1") (pinfunction "1_1") (pintype "passive"))
      (node (ref "SENSORPANEL-0-16") (pin "4") (pinfunction "4_4") (pintype "passive"))
      (node (ref "U6") (pin "3") (pinfunction "+IN_A_3") (pintype "input"))
    )
    (net (code "21") (name "Net-(U6-+IN_B)") (class "Default")
      (node (ref "R22") (pin "1") (pinfunction "1_1") (pintype "passive"))
      (node (ref "SENSORPANEL-0-16") (pin "3") (pinfunction "3_3") (pintype "passive"))
      (node (ref "U6") (pin "5") (pinfunction "+IN_B_5") (pintype "input"))
    )
    (net (code "22") (name "Net-(U6--IN_A)") (class "Default")
      (node (ref "R20") (pin "2") (pinfunction "2_2") (pintype "passive"))
      (node (ref "R84") (pin "1") (pinfunction "1_1") (pintype "passive"))
      (node (ref "U6") (pin "2") (pinfunction "-IN_A_2") (pintype "input"))
    )
    (net (code "23") (name "Net-(U6--IN_B)") (class "Default")
      (node (ref "R23") (pin "2") (pinfunction "2_2") (pintype "passive"))
      (node (ref "R85") (pin "1") (pinfunction "1_1") (pintype "passive"))
      (node (ref "U6") (pin "6") (pinfunction "-IN_B_6") (pintype "input"))
    )
    (net (code "24") (name "Net-(U7-+IN_A)") (class "Default")
      (node (ref "R25") (pin "1") (pinfunction "1_1") (pintype "passive"))
      (node (ref "SENSORPANEL-0-16") (pin "6") (pinfunction "6_6") (pintype "passive"))
      (node (ref "U7") (pin "3") (pinfunction "+IN_A_3") (pintype "input"))
    )
    (net (code "25") (name "Net-(U7-+IN_B)") (class "Default")
      (node (ref "R26") (pin "1") (pinfunction "1_1") (pintype "passive"))
      (node (ref "SENSORPANEL-0-16") (pin "5") (pinfunction "5_5") (pintype "passive"))
      (node (ref "U7") (pin "5") (pinfunction "+IN_B_5") (pintype "input"))
    )
    (net (code "26") (name "Net-(U7--IN_A)") (class "Default")
      (node (ref "R24") (pin "1") (pinfunction "1_1") (pintype "passive"))
      (node (ref "R86") (pin "2") (pinfunction "2_2") (pintype "passive"))
      (node (ref "U7") (pin "2") (pinfunction "-IN_A_2") (pintype "input"))
    )
    (net (code "27") (name "Net-(U7--IN_B)") (class "Default")
      (node (ref "R27") (pin "2") (pinfunction "2_2") (pintype "passive"))
      (node (ref "R87") (pin "1") (pinfunction "1_1") (pintype "passive"))
      (node (ref "U7") (pin "6") (pinfunction "-IN_B_6") (pintype "input"))
    )
    (net (code "28") (name "Net-(U8-+IN_A)") (class "Default")
      (node (ref "R29") (pin "1") (pinfunction "1_1") (pintype "passive"))
      (node (ref "SENSORPANEL-0-16") (pin "8") (pinfunction "8_8") (pintype "passive"))
      (node (ref "U8") (pin "3") (pinfunction "+IN_A_3") (pintype "input"))
    )
    (net (code "29") (name "Net-(U8-+IN_B)") (class "Default")
      (node (ref "R30") (pin "1") (pinfunction "1_1") (pintype "passive"))
      (node (ref "SENSORPANEL-0-16") (pin "7") (pinfunction "7_7") (pintype "passive"))
      (node (ref "U8") (pin "5") (pinfunction "+IN_B_5") (pintype "input"))
    )
    (net (code "30") (name "Net-(U8--IN_A)") (class "Default")
      (node (ref "R28") (pin "2") (pinfunction "2_2") (pintype "passive"))
      (node (ref "R88") (pin "1") (pinfunction "1_1") (pintype "passive"))
      (node (ref "U8") (pin "2") (pinfunction "-IN_A_2") (pintype "input"))
    )
    (net (code "31") (name "Net-(U8--IN_B)") (class "Default")
      (node (ref "R31") (pin "2") (pinfunction "2_2") (pintype "passive"))
      (node (ref "R89") (pin "1") (pinfunction "1_1") (pintype "passive"))
      (node (ref "U8") (pin "6") (pinfunction "-IN_B_6") (pintype "input"))
    )
    (net (code "32") (name "Net-(U9-+IN_A)") (class "Default")
      (node (ref "R33") (pin "1") (pinfunction "1_1") (pintype "passive"))
      (node (ref "SENSORPANEL-0-16") (pin "10") (pinfunction "10_10") (pintype "passive"))
      (node (ref "U9") (pin "3") (pinfunction "+IN_A_3") (pintype "input"))
    )
    (net (code "33") (name "Net-(U9-+IN_B)") (class "Default")
      (node (ref "R34") (pin "1") (pinfunction "1_1") (pintype "passive"))
      (node (ref "SENSORPANEL-0-16") (pin "9") (pinfunction "9_9") (pintype "passive"))
      (node (ref "U9") (pin "5") (pinfunction "+IN_B_5") (pintype "input"))
    )
    (net (code "34") (name "Net-(U9--IN_A)") (class "Default")
      (node (ref "R32") (pin "1") (pinfunction "1_1") (pintype "passive"))
      (node (ref "R90") (pin "2") (pinfunction "2_2") (pintype "passive"))
      (node (ref "U9") (pin "2") (pinfunction "-IN_A_2") (pintype "input"))
    )
    (net (code "35") (name "Net-(U9--IN_B)") (class "Default")
      (node (ref "R35") (pin "2") (pinfunction "2_2") (pintype "passive"))
      (node (ref "R91") (pin "1") (pinfunction "1_1") (pintype "passive"))
      (node (ref "U9") (pin "6") (pinfunction "-IN_B_6") (pintype "input"))
    )
    (net (code "36") (name "Net-(U10-+IN_A)") (class "Default")
      (node (ref "R37") (pin "1") (pinfunction "1_1") (pintype "passive"))
      (node (ref "SENSORPANEL-0-16") (pin "12") (pinfunction "12_12") (pintype "passive"))
      (node (ref "U10") (pin "3") (pinfunction "+IN_A_3") (pintype "input"))
    )
    (net (code "37") (name "Net-(U10-+IN_B)") (class "Default")
      (node (ref "R38") (pin "1") (pinfunction "1_1") (pintype "passive"))
      (node (ref "SENSORPANEL-0-16") (pin "11") (pinfunction "11_11") (pintype "passive"))
      (node (ref "U10") (pin "5") (pinfunction "+IN_B_5") (pintype "input"))
    )
    (net (code "38") (name "Net-(U10--IN_A)") (class "Default")
      (node (ref "R36") (pin "1") (pinfunction "1_1") (pintype "passive"))
      (node (ref "R92") (pin "2") (pinfunction "2_2") (pintype "passive"))
      (node (ref "U10") (pin "2") (pinfunction "-IN_A_2") (pintype "input"))
    )
    (net (code "39") (name "Net-(U10--IN_B)") (class "Default")
      (node (ref "R39") (pin "2") (pinfunction "2_2") (pintype "passive"))
      (node (ref "R93") (pin "1") (pinfunction "1_1") (pintype "passive"))
      (node (ref "U10") (pin "6") (pinfunction "-IN_B_6") (pintype "input"))
    )
    (net (code "40") (name "Net-(U10-OUT_A)") (class "Default")
      (node (ref "R36") (pin "2") (pinfunction "2_2") (pintype "passive"))
      (node (ref "U10") (pin "1") (pinfunction "OUT_A_1") (pintype "output"))
      (node (ref "U14") (pin "12") (pinfunction "Y3_12") (pintype "bidirectional"))
    )
    (net (code "41") (name "Net-(U10-OUT_B)") (class "Default")
      (node (ref "R93") (pin "2") (pinfunction "2_2") (pintype "passive"))
      (node (ref "U10") (pin "7") (pinfunction "OUT_B_7") (pintype "output"))
      (node (ref "U14") (pin "15") (pinfunction "Y2_15") (pintype "bidirectional"))
    )
    (net (code "42") (name "Net-(U11-+IN_A)") (class "Default")
      (node (ref "R41") (pin "1") (pinfunction "1_1") (pintype "passive"))
      (node (ref "SENSORPANEL-0-16") (pin "14") (pinfunction "14_14") (pintype "passive"))
      (node (ref "U11") (pin "3") (pinfunction "+IN_A_3") (pintype "input"))
    )
    (net (code "43") (name "Net-(U11-+IN_B)") (class "Default")
      (node (ref "R42") (pin "1") (pinfunction "1_1") (pintype "passive"))
      (node (ref "SENSORPANEL-0-16") (pin "13") (pinfunction "13_13") (pintype "passive"))
      (node (ref "U11") (pin "5") (pinfunction "+IN_B_5") (pintype "input"))
    )
    (net (code "44") (name "Net-(U11--IN_A)") (class "Default")
      (node (ref "R40") (pin "2") (pinfunction "2_2") (pintype "passive"))
      (node (ref "R94") (pin "1") (pinfunction "1_1") (pintype "passive"))
      (node (ref "U11") (pin "2") (pinfunction "-IN_A_2") (pintype "input"))
    )
    (net (code "45") (name "Net-(U11--IN_B)") (class "Default")
      (node (ref "R43") (pin "2") (pinfunction "2_2") (pintype "passive"))
      (node (ref "R95") (pin "1") (pinfunction "1_1") (pintype "passive"))
      (node (ref "U11") (pin "6") (pinfunction "-IN_B_6") (pintype "input"))
    )
    (net (code "46") (name "Net-(U11-OUT_A)") (class "Default")
      (node (ref "R94") (pin "2") (pinfunction "2_2") (pintype "passive"))
      (node (ref "U11") (pin "1") (pinfunction "OUT_A_1") (pintype "output"))
      (node (ref "U14") (pin "5") (pinfunction "Y5_5") (pintype "bidirectional"))
    )
    (net (code "47") (name "Net-(U11-OUT_B)") (class "Default")
      (node (ref "R95") (pin "2") (pinfunction "2_2") (pintype "passive"))
      (node (ref "U11") (pin "7") (pinfunction "OUT_B_7") (pintype "output"))
      (node (ref "U14") (pin "1") (pinfunction "Y4_1") (pintype "bidirectional"))
    )
    (net (code "48") (name "Net-(U12-+IN_A)") (class "Default")
      (node (ref "R45") (pin "1") (pinfunction "1_1") (pintype "passive"))
      (node (ref "SENSORPANEL-0-16") (pin "16") (pinfunction "16_16") (pintype "passive"))
      (node (ref "U12") (pin "3") (pinfunction "+IN_A_3") (pintype "input"))
    )
    (net (code "49") (name "Net-(U12-+IN_B)") (class "Default")
      (node (ref "R46") (pin "1") (pinfunction "1_1") (pintype "passive"))
      (node (ref "SENSORPANEL-0-16") (pin "15") (pinfunction "15_15") (pintype "passive"))
      (node (ref "U12") (pin "5") (pinfunction "+IN_B_5") (pintype "input"))
    )
    (net (code "50") (name "Net-(U12--IN_A)") (class "Default")
      (node (ref "R44") (pin "2") (pinfunction "2_2") (pintype "passive"))
      (node (ref "R96") (pin "1") (pinfunction "1_1") (pintype "passive"))
      (node (ref "U12") (pin "2") (pinfunction "-IN_A_2") (pintype "input"))
    )
    (net (code "51") (name "Net-(U12--IN_B)") (class "Default")
      (node (ref "R47") (pin "2") (pinfunction "2_2") (pintype "passive"))
      (node (ref "R97") (pin "1") (pinfunction "1_1") (pintype "passive"))
      (node (ref "U12") (pin "6") (pinfunction "-IN_B_6") (pintype "input"))
    )
    (net (code "52") (name "Net-(U12-OUT_A)") (class "Default")
      (node (ref "R96") (pin "2") (pinfunction "2_2") (pintype "passive"))
      (node (ref "U12") (pin "1") (pinfunction "OUT_A_1") (pintype "output"))
      (node (ref "U14") (pin "4") (pinfunction "Y7_4") (pintype "bidirectional"))
    )
    (net (code "53") (name "Net-(U12-OUT_B)") (class "Default")
      (node (ref "R97") (pin "2") (pinfunction "2_2") (pintype "passive"))
      (node (ref "U12") (pin "7") (pinfunction "OUT_B_7") (pintype "output"))
      (node (ref "U14") (pin "2") (pinfunction "Y6_2") (pintype "bidirectional"))
    )
    (net (code "54") (name "Net-(U13-Y0)") (class "Default")
      (node (ref "R83") (pin "2") (pinfunction "2_2") (pintype "passive"))
      (node (ref "U13") (pin "13") (pinfunction "Y0_13") (pintype "bidirectional"))
      (node (ref "U5") (pin "7") (pinfunction "OUT_B_7") (pintype "output"))
    )
    (net (code "55") (name "Net-(U13-Y1)") (class "Default")
      (node (ref "R82") (pin "2") (pinfunction "2_2") (pintype "passive"))
      (node (ref "U13") (pin "14") (pinfunction "Y1_14") (pintype "bidirectional"))
      (node (ref "U5") (pin "1") (pinfunction "OUT_A_1") (pintype "output"))
    )
    (net (code "56") (name "Net-(U13-Y2)") (class "Default")
      (node (ref "R85") (pin "2") (pinfunction "2_2") (pintype "passive"))
      (node (ref "U13") (pin "15") (pinfunction "Y2_15") (pintype "bidirectional"))
      (node (ref "U6") (pin "7") (pinfunction "OUT_B_7") (pintype "output"))
    )
    (net (code "57") (name "Net-(U13-Y3)") (class "Default")
      (node (ref "R84") (pin "2") (pinfunction "2_2") (pintype "passive"))
      (node (ref "U13") (pin "12") (pinfunction "Y3_12") (pintype "bidirectional"))
      (node (ref "U6") (pin "1") (pinfunction "OUT_A_1") (pintype "output"))
    )
    (net (code "58") (name "Net-(U13-Y4)") (class "Default")
      (node (ref "R87") (pin "2") (pinfunction "2_2") (pintype "passive"))
      (node (ref "U13") (pin "1") (pinfunction "Y4_1") (pintype "bidirectional"))
      (node (ref "U7") (pin "7") (pinfunction "OUT_B_7") (pintype "output"))
    )
    (net (code "59") (name "Net-(U13-Y5)") (class "Default")
      (node (ref "R24") (pin "2") (pinfunction "2_2") (pintype "passive"))
      (node (ref "U13") (pin "5") (pinfunction "Y5_5") (pintype "bidirectional"))
      (node (ref "U7") (pin "1") (pinfunction "OUT_A_1") (pintype "output"))
    )
    (net (code "60") (name "Net-(U13-Y6)") (class "Default")
      (node (ref "R89") (pin "2") (pinfunction "2_2") (pintype "passive"))
      (node (ref "U13") (pin "2") (pinfunction "Y6_2") (pintype "bidirectional"))
      (node (ref "U8") (pin "7") (pinfunction "OUT_B_7") (pintype "output"))
    )
    (net (code "61") (name "Net-(U13-Y7)") (class "Default")
      (node (ref "R88") (pin "2") (pinfunction "2_2") (pintype "passive"))
      (node (ref "U13") (pin "4") (pinfunction "Y7_4") (pintype "bidirectional"))
      (node (ref "U8") (pin "1") (pinfunction "OUT_A_1") (pintype "output"))
    )
    (net (code "62") (name "Net-(U14-Y0)") (class "Default")
      (node (ref "R91") (pin "2") (pinfunction "2_2") (pintype "passive"))
      (node (ref "U14") (pin "13") (pinfunction "Y0_13") (pintype "bidirectional"))
      (node (ref "U9") (pin "7") (pinfunction "OUT_B_7") (pintype "output"))
    )
    (net (code "63") (name "Net-(U14-Y1)") (class "Default")
      (node (ref "R32") (pin "2") (pinfunction "2_2") (pintype "passive"))
      (node (ref "U14") (pin "14") (pinfunction "Y1_14") (pintype "bidirectional"))
      (node (ref "U9") (pin "1") (pinfunction "OUT_A_1") (pintype "output"))
    )
    (net (code "64") (name "Net-(U15-+IN_A)") (class "Default")
      (node (ref "R49") (pin "1") (pinfunction "1_1") (pintype "passive"))
      (node (ref "SENSORPANEL-16-31") (pin "2") (pinfunction "2_2") (pintype "passive"))
      (node (ref "U15") (pin "3") (pinfunction "+IN_A_3") (pintype "input"))
    )
    (net (code "65") (name "Net-(U15-+IN_B)") (class "Default")
      (node (ref "R50") (pin "1") (pinfunction "1_1") (pintype "passive"))
      (node (ref "SENSORPANEL-16-31") (pin "1") (pinfunction "1_1") (pintype "passive"))
      (node (ref "U15") (pin "5") (pinfunction "+IN_B_5") (pintype "input"))
    )
    (net (code "66") (name "Net-(U15--IN_A)") (class "Default")
      (node (ref "R2") (pin "1") (pinfunction "1_1") (pintype "passive"))
      (node (ref "R3") (pin "2") (pinfunction "2_2") (pintype "passive"))
      (node (ref "U15") (pin "2") (pinfunction "-IN_A_2") (pintype "input"))
    )
    (net (code "67") (name "Net-(U15--IN_B)") (class "Default")
      (node (ref "R4") (pin "2") (pinfunction "2_2") (pintype "passive"))
      (node (ref "R5") (pin "1") (pinfunction "1_1") (pintype "passive"))
      (node (ref "U15") (pin "6") (pinfunction "-IN_B_6") (pintype "input"))
    )
    (net (code "68") (name "Net-(U15-OUT_A)") (class "Default")
      (node (ref "R2") (pin "2") (pinfunction "2_2") (pintype "passive"))
      (node (ref "U15") (pin "1") (pinfunction "OUT_A_1") (pintype "output"))
      (node (ref "U23") (pin "14") (pinfunction "Y1_14") (pintype "bidirectional"))
    )
    (net (code "69") (name "Net-(U15-OUT_B)") (class "Default")
      (node (ref "R5") (pin "2") (pinfunction "2_2") (pintype "passive"))
      (node (ref "U15") (pin "7") (pinfunction "OUT_B_7") (pintype "output"))
      (node (ref "U23") (pin "13") (pinfunction "Y0_13") (pintype "bidirectional"))
    )
    (net (code "70") (name "Net-(U16-+IN_A)") (class "Default")
      (node (ref "R53") (pin "1") (pinfunction "1_1") (pintype "passive"))
      (node (ref "SENSORPANEL-16-31") (pin "4") (pinfunction "4_4") (pintype "passive"))
      (node (ref "U16") (pin "3") (pinfunction "+IN_A_3") (pintype "input"))
    )
    (net (code "71") (name "Net-(U16-+IN_B)") (class "Default")
      (node (ref "R54") (pin "1") (pinfunction "1_1") (pintype "passive"))
      (node (ref "SENSORPANEL-16-31") (pin "3") (pinfunction "3_3") (pintype "passive"))
      (node (ref "U16") (pin "5") (pinfunction "+IN_B_5") (pintype "input"))
    )
    (net (code "72") (name "Net-(U16--IN_A)") (class "Default")
      (node (ref "R6") (pin "2") (pinfunction "2_2") (pintype "passive"))
      (node (ref "R7") (pin "1") (pinfunction "1_1") (pintype "passive"))
      (node (ref "U16") (pin "2") (pinfunction "-IN_A_2") (pintype "input"))
    )
    (net (code "73") (name "Net-(U16--IN_B)") (class "Default")
      (node (ref "R8") (pin "2") (pinfunction "2_2") (pintype "passive"))
      (node (ref "R9") (pin "1") (pinfunction "1_1") (pintype "passive"))
      (node (ref "U16") (pin "6") (pinfunction "-IN_B_6") (pintype "input"))
    )
    (net (code "74") (name "Net-(U16-OUT_A)") (class "Default")
      (node (ref "R7") (pin "2") (pinfunction "2_2") (pintype "passive"))
      (node (ref "U16") (pin "1") (pinfunction "OUT_A_1") (pintype "output"))
      (node (ref "U23") (pin "12") (pinfunction "Y3_12") (pintype "bidirectional"))
    )
    (net (code "75") (name "Net-(U16-OUT_B)") (class "Default")
      (node (ref "R9") (pin "2") (pinfunction "2_2") (pintype "passive"))
      (node (ref "U16") (pin "7") (pinfunction "OUT_B_7") (pintype "output"))
      (node (ref "U23") (pin "15") (pinfunction "Y2_15") (pintype "bidirectional"))
    )
    (net (code "76") (name "Net-(U17-+IN_A)") (class "Default")
      (node (ref "R57") (pin "1") (pinfunction "1_1") (pintype "passive"))
      (node (ref "SENSORPANEL-16-31") (pin "6") (pinfunction "6_6") (pintype "passive"))
      (node (ref "U17") (pin "3") (pinfunction "+IN_A_3") (pintype "input"))
    )
    (net (code "77") (name "Net-(U17-+IN_B)") (class "Default")
      (node (ref "R58") (pin "1") (pinfunction "1_1") (pintype "passive"))
      (node (ref "SENSORPANEL-16-31") (pin "5") (pinfunction "5_5") (pintype "passive"))
      (node (ref "U17") (pin "5") (pinfunction "+IN_B_5") (pintype "input"))
    )
    (net (code "78") (name "Net-(U17--IN_A)") (class "Default")
      (node (ref "R10") (pin "1") (pinfunction "1_1") (pintype "passive"))
      (node (ref "R11") (pin "2") (pinfunction "2_2") (pintype "passive"))
      (node (ref "U17") (pin "2") (pinfunction "-IN_A_2") (pintype "input"))
    )
    (net (code "79") (name "Net-(U17--IN_B)") (class "Default")
      (node (ref "R12") (pin "2") (pinfunction "2_2") (pintype "passive"))
      (node (ref "R13") (pin "1") (pinfunction "1_1") (pintype "passive"))
      (node (ref "U17") (pin "6") (pinfunction "-IN_B_6") (pintype "input"))
    )
    (net (code "80") (name "Net-(U17-OUT_A)") (class "Default")
      (node (ref "R10") (pin "2") (pinfunction "2_2") (pintype "passive"))
      (node (ref "U17") (pin "1") (pinfunction "OUT_A_1") (pintype "output"))
      (node (ref "U23") (pin "5") (pinfunction "Y5_5") (pintype "bidirectional"))
    )
    (net (code "81") (name "Net-(U17-OUT_B)") (class "Default")
      (node (ref "R13") (pin "2") (pinfunction "2_2") (pintype "passive"))
      (node (ref "U17") (pin "7") (pinfunction "OUT_B_7") (pintype "output"))
      (node (ref "U23") (pin "1") (pinfunction "Y4_1") (pintype "bidirectional"))
    )
    (net (code "82") (name "Net-(U18-+IN_A)") (class "Default")
      (node (ref "R61") (pin "1") (pinfunction "1_1") (pintype "passive"))
      (node (ref "SENSORPANEL-16-31") (pin "8") (pinfunction "8_8") (pintype "passive"))
      (node (ref "U18") (pin "3") (pinfunction "+IN_A_3") (pintype "input"))
    )
    (net (code "83") (name "Net-(U18-+IN_B)") (class "Default")
      (node (ref "R62") (pin "1") (pinfunction "1_1") (pintype "passive"))
      (node (ref "SENSORPANEL-16-31") (pin "7") (pinfunction "7_7") (pintype "passive"))
      (node (ref "U18") (pin "5") (pinfunction "+IN_B_5") (pintype "input"))
    )
    (net (code "84") (name "Net-(U18--IN_A)") (class "Default")
      (node (ref "R14") (pin "2") (pinfunction "2_2") (pintype "passive"))
      (node (ref "R15") (pin "1") (pinfunction "1_1") (pintype "passive"))
      (node (ref "U18") (pin "2") (pinfunction "-IN_A_2") (pintype "input"))
    )
    (net (code "85") (name "Net-(U18--IN_B)") (class "Default")
      (node (ref "R48") (pin "2") (pinfunction "2_2") (pintype "passive"))
      (node (ref "R51") (pin "1") (pinfunction "1_1") (pintype "passive"))
      (node (ref "U18") (pin "6") (pinfunction "-IN_B_6") (pintype "input"))
    )
    (net (code "86") (name "Net-(U18-OUT_A)") (class "Default")
      (node (ref "R15") (pin "2") (pinfunction "2_2") (pintype "passive"))
      (node (ref "U18") (pin "1") (pinfunction "OUT_A_1") (pintype "output"))
      (node (ref "U23") (pin "4") (pinfunction "Y7_4") (pintype "bidirectional"))
    )
    (net (code "87") (name "Net-(U18-OUT_B)") (class "Default")
      (node (ref "R51") (pin "2") (pinfunction "2_2") (pintype "passive"))
      (node (ref "U18") (pin "7") (pinfunction "OUT_B_7") (pintype "output"))
      (node (ref "U23") (pin "2") (pinfunction "Y6_2") (pintype "bidirectional"))
    )
    (net (code "88") (name "Net-(U19-+IN_A)") (class "Default")
      (node (ref "R65") (pin "1") (pinfunction "1_1") (pintype "passive"))
      (node (ref "SENSORPANEL-16-31") (pin "10") (pinfunction "10_10") (pintype "passive"))
      (node (ref "U19") (pin "3") (pinfunction "+IN_A_3") (pintype "input"))
    )
    (net (code "89") (name "Net-(U19-+IN_B)") (class "Default")
      (node (ref "R66") (pin "1") (pinfunction "1_1") (pintype "passive"))
      (node (ref "SENSORPANEL-16-31") (pin "9") (pinfunction "9_9") (pintype "passive"))
      (node (ref "U19") (pin "5") (pinfunction "+IN_B_5") (pintype "input"))
    )
    (net (code "90") (name "Net-(U19--IN_A)") (class "Default")
      (node (ref "R52") (pin "2") (pinfunction "2_2") (pintype "passive"))
      (node (ref "R55") (pin "1") (pinfunction "1_1") (pintype "passive"))
      (node (ref "U19") (pin "2") (pinfunction "-IN_A_2") (pintype "input"))
    )
    (net (code "91") (name "Net-(U19--IN_B)") (class "Default")
      (node (ref "R56") (pin "2") (pinfunction "2_2") (pintype "passive"))
      (node (ref "R59") (pin "1") (pinfunction "1_1") (pintype "passive"))
      (node (ref "U19") (pin "6") (pinfunction "-IN_B_6") (pintype "input"))
    )
    (net (code "92") (name "Net-(U19-OUT_A)") (class "Default")
      (node (ref "R55") (pin "2") (pinfunction "2_2") (pintype "passive"))
      (node (ref "U19") (pin "1") (pinfunction "OUT_A_1") (pintype "output"))
      (node (ref "U24") (pin "14") (pinfunction "Y1_14") (pintype "bidirectional"))
    )
    (net (code "93") (name "Net-(U19-OUT_B)") (class "Default")
      (node (ref "R59") (pin "2") (pinfunction "2_2") (pintype "passive"))
      (node (ref "U19") (pin "7") (pinfunction "OUT_B_7") (pintype "output"))
      (node (ref "U24") (pin "13") (pinfunction "Y0_13") (pintype "bidirectional"))
    )
    (net (code "94") (name "Net-(U20-+IN_A)") (class "Default")
      (node (ref "R69") (pin "1") (pinfunction "1_1") (pintype "passive"))
      (node (ref "SENSORPANEL-16-31") (pin "12") (pinfunction "12_12") (pintype "passive"))
      (node (ref "U20") (pin "3") (pinfunction "+IN_A_3") (pintype "input"))
    )
    (net (code "95") (name "Net-(U20-+IN_B)") (class "Default")
      (node (ref "R70") (pin "1") (pinfunction "1_1") (pintype "passive"))
      (node (ref "SENSORPANEL-16-31") (pin "11") (pinfunction "11_11") (pintype "passive"))
      (node (ref "U20") (pin "5") (pinfunction "+IN_B_5") (pintype "input"))
    )
    (net (code "96") (name "Net-(U20--IN_A)") (class "Default")
      (node (ref "R60") (pin "2") (pinfunction "2_2") (pintype "passive"))
      (node (ref "R63") (pin "1") (pinfunction "1_1") (pintype "passive"))
      (node (ref "U20") (pin "2") (pinfunction "-IN_A_2") (pintype "input"))
    )
    (net (code "97") (name "Net-(U20--IN_B)") (class "Default")
      (node (ref "R64") (pin "2") (pinfunction "2_2") (pintype "passive"))
      (node (ref "R67") (pin "1") (pinfunction "1_1") (pintype "passive"))
      (node (ref "U20") (pin "6") (pinfunction "-IN_B_6") (pintype "input"))
    )
    (net (code "98") (name "Net-(U20-OUT_A)") (class "Default")
      (node (ref "R63") (pin "2") (pinfunction "2_2") (pintype "passive"))
      (node (ref "U20") (pin "1") (pinfunction "OUT_A_1") (pintype "output"))
      (node (ref "U24") (pin "12") (pinfunction "Y3_12") (pintype "bidirectional"))
    )
    (net (code "99") (name "Net-(U20-OUT_B)") (class "Default")
      (node (ref "R67") (pin "2") (pinfunction "2_2") (pintype "passive"))
      (node (ref "U20") (pin "7") (pinfunction "OUT_B_7") (pintype "output"))
      (node (ref "U24") (pin "15") (pinfunction "Y2_15") (pintype "bidirectional"))
    )
    (net (code "100") (name "Net-(U21-+IN_A)") (class "Default")
      (node (ref "R73") (pin "1") (pinfunction "1_1") (pintype "passive"))
      (node (ref "SENSORPANEL-16-31") (pin "14") (pinfunction "14_14") (pintype "passive"))
      (node (ref "U21") (pin "3") (pinfunction "+IN_A_3") (pintype "input"))
    )
    (net (code "101") (name "Net-(U21-+IN_B)") (class "Default")
      (node (ref "R74") (pin "1") (pinfunction "1_1") (pintype "passive"))
      (node (ref "SENSORPANEL-16-31") (pin "13") (pinfunction "13_13") (pintype "passive"))
      (node (ref "U21") (pin "5") (pinfunction "+IN_B_5") (pintype "input"))
    )
    (net (code "102") (name "Net-(U21--IN_A)") (class "Default")
      (node (ref "R68") (pin "2") (pinfunction "2_2") (pintype "passive"))
      (node (ref "R71") (pin "1") (pinfunction "1_1") (pintype "passive"))
      (node (ref "U21") (pin "2") (pinfunction "-IN_A_2") (pintype "input"))
    )
    (net (code "103") (name "Net-(U21--IN_B)") (class "Default")
      (node (ref "R72") (pin "2") (pinfunction "2_2") (pintype "passive"))
      (node (ref "R75") (pin "1") (pinfunction "1_1") (pintype "passive"))
      (node (ref "U21") (pin "6") (pinfunction "-IN_B_6") (pintype "input"))
    )
    (net (code "104") (name "Net-(U21-OUT_A)") (class "Default")
      (node (ref "R71") (pin "2") (pinfunction "2_2") (pintype "passive"))
      (node (ref "U21") (pin "1") (pinfunction "OUT_A_1") (pintype "output"))
      (node (ref "U24") (pin "5") (pinfunction "Y5_5") (pintype "bidirectional"))
    )
    (net (code "105") (name "Net-(U21-OUT_B)") (class "Default")
      (node (ref "R75") (pin "2") (pinfunction "2_2") (pintype "passive"))
      (node (ref "U21") (pin "7") (pinfunction "OUT_B_7") (pintype "output"))
      (node (ref "U24") (pin "1") (pinfunction "Y4_1") (pintype "bidirectional"))
    )
    (net (code "106") (name "Net-(U22-+IN_A)") (class "Default")
      (node (ref "R77") (pin "1") (pinfunction "1_1") (pintype "passive"))
      (node (ref "SENSORPANEL-16-31") (pin "16") (pinfunction "16_16") (pintype "passive"))
      (node (ref "U22") (pin "3") (pinfunction "+IN_A_3") (pintype "input"))
    )
    (net (code "107") (name "Net-(U22-+IN_B)") (class "Default")
      (node (ref "R78") (pin "1") (pinfunction "1_1") (pintype "passive"))
      (node (ref "SENSORPANEL-16-31") (pin "15") (pinfunction "15_15") (pintype "passive"))
      (node (ref "U22") (pin "5") (pinfunction "+IN_B_5") (pintype "input"))
    )
    (net (code "108") (name "Net-(U22--IN_A)") (class "Default")
      (node (ref "R76") (pin "2") (pinfunction "2_2") (pintype "passive"))
      (node (ref "R80") (pin "1") (pinfunction "1_1") (pintype "passive"))
      (node (ref "U22") (pin "2") (pinfunction "-IN_A_2") (pintype "input"))
    )
    (net (code "109") (name "Net-(U22--IN_B)") (class "Default")
      (node (ref "R79") (pin "2") (pinfunction "2_2") (pintype "passive"))
      (node (ref "R81") (pin "1") (pinfunction "1_1") (pintype "passive"))
      (node (ref "U22") (pin "6") (pinfunction "-IN_B_6") (pintype "input"))
    )
    (net (code "110") (name "Net-(U22-OUT_A)") (class "Default")
      (node (ref "R80") (pin "2") (pinfunction "2_2") (pintype "passive"))
      (node (ref "U22") (pin "1") (pinfunction "OUT_A_1") (pintype "output"))
      (node (ref "U24") (pin "4") (pinfunction "Y7_4") (pintype "bidirectional"))
    )
    (net (code "111") (name "Net-(U22-OUT_B)") (class "Default")
      (node (ref "R81") (pin "2") (pinfunction "2_2") (pintype "passive"))
      (node (ref "U22") (pin "7") (pinfunction "OUT_B_7") (pintype "output"))
      (node (ref "U24") (pin "2") (pinfunction "Y6_2") (pintype "bidirectional"))
    )
    (net (code "112") (name "unconnected-(IC2-QH*-Pad9)") (class "Default")
      (node (ref "IC2") (pin "9") (pinfunction "QH*_9") (pintype "tri_state"))
    )
    (net (code "113") (name "unconnected-(IC2-QH-Pad7)") (class "Default")
      (node (ref "IC2") (pin "7") (pinfunction "QH_7") (pintype "tri_state"))
    )
    (net (code "114") (name "unconnected-(MOTHERBOARD-Pad7)") (class "Default")
      (node (ref "MOTHERBOARD") (pin "7") (pinfunction "7_7") (pintype "passive"))
    )
  )
)
